# Peripherals.net
KiCad netlist of a schematic drawn in Altium Designer
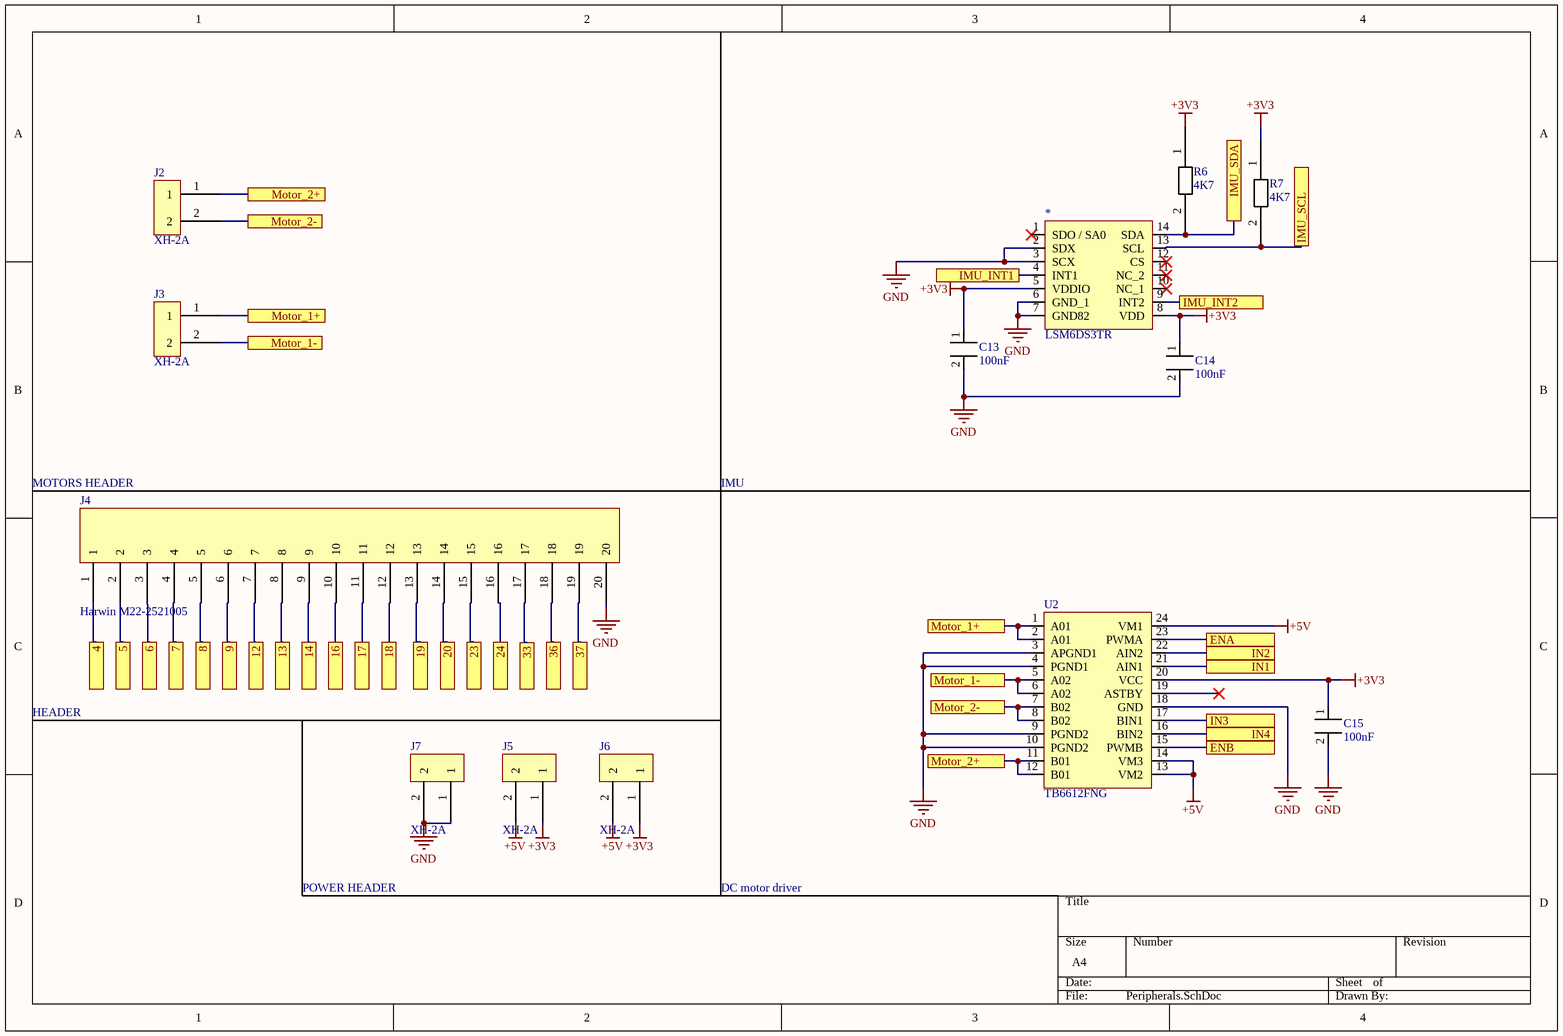
[diagram p0: Peripherals.SchDoc]

(export (version "E")
  (design (tool "Eeschema 10.0.6"))
  (components
    (comp (ref "*")
      (value "LSM6DS3TR")
      (footprint "LSM6DS3TR")
      (libsource (lib "Schlib1") (part "LSM6DS3TR"))
    )
    (comp (ref "C13") (value "100nF") (footprint "Condo") (libsource (lib "Schlib1") (part "CAPA")))
    (comp (ref "C14") (value "100nF") (footprint "Condo") (libsource (lib "Schlib1") (part "CAPA")))
    (comp (ref "C15") (value "100nF") (footprint "Condo") (libsource (lib "Schlib1") (part "CAPA")))
    (comp (ref "J2") (value "XH-2A") (footprint "XH-2A") (libsource (lib "") (part "XH-2A_1")))
    (comp (ref "J3") (value "XH-2A") (footprint "XH-2A") (libsource (lib "") (part "XH-2A_1")))
    (comp (ref "J4")
      (value "Harwin M22-2521005")
      (footprint "M22-2521005")
      (libsource (lib "Schlib1") (part "Harwin M22-2521005"))
    )
    (comp (ref "J5") (value "XH-2A") (footprint "XH-2A") (libsource (lib "Schlib1") (part "XH-2A")))
    (comp (ref "J6") (value "XH-2A") (footprint "XH-2A") (libsource (lib "Schlib1") (part "XH-2A")))
    (comp (ref "J7") (value "XH-2A") (footprint "XH-2A") (libsource (lib "Schlib1") (part "XH-2A")))
    (comp (ref "R6") (value "4K7") (footprint "Resistor") (libsource (lib "Schlib1") (part "Resistor")))
    (comp (ref "R7") (value "4K7") (footprint "Resistor") (libsource (lib "Schlib1") (part "Resistor")))
    (comp (ref "U2")
      (value "TB6612FNG")
      (footprint "TB6612FNG")
      (libsource (lib "Schlib1") (part "TB6612FNG"))
    )
  )
  (nets
    (net (code "1") (name "+3V3") (class "Default")
      (node (ref "*") (pin "5") (pinfunction "VDDIO_5") (pintype "passive"))
      (node (ref "*") (pin "8") (pinfunction "VDD_8") (pintype "passive"))
      (node (ref "C13") (pin "1") (pinfunction "IN_1") (pintype "passive"))
      (node (ref "C14") (pin "1") (pinfunction "IN_1") (pintype "passive"))
      (node (ref "C15") (pin "1") (pinfunction "IN_1") (pintype "passive"))
      (node (ref "J5") (pin "1") (pinfunction "1_1") (pintype "passive"))
      (node (ref "J6") (pin "1") (pinfunction "1_1") (pintype "passive"))
      (node (ref "R6") (pin "1") (pinfunction "1_1") (pintype "passive"))
      (node (ref "R7") (pin "1") (pinfunction "1_1") (pintype "passive"))
      (node (ref "U2") (pin "20") (pinfunction "VCC_20") (pintype "passive"))
    )
    (net (code "2") (name "+5V") (class "Default")
      (node (ref "J5") (pin "2") (pinfunction "2_2") (pintype "passive"))
      (node (ref "J6") (pin "2") (pinfunction "2_2") (pintype "passive"))
      (node (ref "U2") (pin "13") (pinfunction "VM2_13") (pintype "passive"))
      (node (ref "U2") (pin "14") (pinfunction "VM3_14") (pintype "passive"))
      (node (ref "U2") (pin "24") (pinfunction "VM1_24") (pintype "passive"))
    )
    (net (code "3") (name "/4") (class "Default")
      (node (ref "J4") (pin "1") (pinfunction "1_1") (pintype "passive"))
    )
    (net (code "4") (name "/5") (class "Default")
      (node (ref "J4") (pin "2") (pinfunction "2_2") (pintype "passive"))
    )
    (net (code "5") (name "/6") (class "Default")
      (node (ref "J4") (pin "3") (pinfunction "3_3") (pintype "passive"))
    )
    (net (code "6") (name "/7") (class "Default")
      (node (ref "J4") (pin "4") (pinfunction "4_4") (pintype "passive"))
    )
    (net (code "7") (name "/8") (class "Default")
      (node (ref "J4") (pin "5") (pinfunction "5_5") (pintype "passive"))
    )
    (net (code "8") (name "/9") (class "Default")
      (node (ref "J4") (pin "6") (pinfunction "6_6") (pintype "passive"))
    )
    (net (code "9") (name "/12") (class "Default")
      (node (ref "J4") (pin "7") (pinfunction "7_7") (pintype "passive"))
    )
    (net (code "10") (name "/13") (class "Default")
      (node (ref "J4") (pin "8") (pinfunction "8_8") (pintype "passive"))
    )
    (net (code "11") (name "/14") (class "Default")
      (node (ref "J4") (pin "9") (pinfunction "9_9") (pintype "passive"))
    )
    (net (code "12") (name "/16") (class "Default")
      (node (ref "J4") (pin "10") (pinfunction "10_10") (pintype "passive"))
    )
    (net (code "13") (name "/17") (class "Default")
      (node (ref "J4") (pin "11") (pinfunction "11_11") (pintype "passive"))
    )
    (net (code "14") (name "/18") (class "Default")
      (node (ref "J4") (pin "12") (pinfunction "12_12") (pintype "passive"))
    )
    (net (code "15") (name "/19") (class "Default")
      (node (ref "J4") (pin "13") (pinfunction "13_13") (pintype "passive"))
    )
    (net (code "16") (name "/20") (class "Default")
      (node (ref "J4") (pin "14") (pinfunction "14_14") (pintype "passive"))
    )
    (net (code "17") (name "/23") (class "Default")
      (node (ref "J4") (pin "15") (pinfunction "15_15") (pintype "passive"))
    )
    (net (code "18") (name "/24") (class "Default")
      (node (ref "J4") (pin "16") (pinfunction "16_16") (pintype "passive"))
    )
    (net (code "19") (name "/33") (class "Default")
      (node (ref "J4") (pin "17") (pinfunction "17_17") (pintype "passive"))
    )
    (net (code "20") (name "/36") (class "Default")
      (node (ref "J4") (pin "18") (pinfunction "18_18") (pintype "passive"))
    )
    (net (code "21") (name "/37") (class "Default")
      (node (ref "J4") (pin "19") (pinfunction "19_19") (pintype "passive"))
    )
    (net (code "22") (name "/ENA") (class "Default")
      (node (ref "U2") (pin "23") (pinfunction "PWMA_23") (pintype "passive"))
    )
    (net (code "23") (name "/ENB") (class "Default")
      (node (ref "U2") (pin "15") (pinfunction "PWMB_15") (pintype "passive"))
    )
    (net (code "24") (name "/IMU_INT1") (class "Default")
      (node (ref "*") (pin "4") (pinfunction "INT1_4") (pintype "passive"))
    )
    (net (code "25") (name "/IMU_INT2") (class "Default")
      (node (ref "*") (pin "9") (pinfunction "INT2_9") (pintype "passive"))
    )
    (net (code "26") (name "/IMU_SCL") (class "Default")
      (node (ref "*") (pin "13") (pinfunction "SCL_13") (pintype "passive"))
      (node (ref "R7") (pin "2") (pinfunction "2_2") (pintype "passive"))
    )
    (net (code "27") (name "/IMU_SDA") (class "Default")
      (node (ref "*") (pin "14") (pinfunction "SDA_14") (pintype "passive"))
      (node (ref "R6") (pin "2") (pinfunction "2_2") (pintype "passive"))
    )
    (net (code "28") (name "/IN1") (class "Default")
      (node (ref "U2") (pin "21") (pinfunction "AIN1_21") (pintype "passive"))
    )
    (net (code "29") (name "/IN2") (class "Default")
      (node (ref "U2") (pin "22") (pinfunction "AIN2_22") (pintype "passive"))
    )
    (net (code "30") (name "/IN3") (class "Default")
      (node (ref "U2") (pin "17") (pinfunction "BIN1_17") (pintype "passive"))
    )
    (net (code "31") (name "/IN4") (class "Default")
      (node (ref "U2") (pin "16") (pinfunction "BIN2_16") (pintype "passive"))
    )
    (net (code "32") (name "/Motor_1+") (class "Default")
      (node (ref "J3") (pin "1") (pinfunction "1_1") (pintype "passive"))
      (node (ref "U2") (pin "1") (pinfunction "A01_1") (pintype "passive"))
      (node (ref "U2") (pin "2") (pinfunction "A01_2") (pintype "passive"))
    )
    (net (code "33") (name "/Motor_1-") (class "Default")
      (node (ref "J3") (pin "2") (pinfunction "2_2") (pintype "passive"))
      (node (ref "U2") (pin "5") (pinfunction "A02_5") (pintype "passive"))
      (node (ref "U2") (pin "6") (pinfunction "A02_6") (pintype "passive"))
    )
    (net (code "34") (name "/Motor_2+") (class "Default")
      (node (ref "J2") (pin "1") (pinfunction "1_1") (pintype "passive"))
      (node (ref "U2") (pin "11") (pinfunction "B01_11") (pintype "passive"))
      (node (ref "U2") (pin "12") (pinfunction "B01_12") (pintype "passive"))
    )
    (net (code "35") (name "/Motor_2-") (class "Default")
      (node (ref "J2") (pin "2") (pinfunction "2_2") (pintype "passive"))
      (node (ref "U2") (pin "7") (pinfunction "B02_7") (pintype "passive"))
      (node (ref "U2") (pin "8") (pinfunction "B02_8") (pintype "passive"))
    )
    (net (code "36") (name "GND") (class "Default")
      (node (ref "*") (pin "2") (pinfunction "SDX_2") (pintype "passive"))
      (node (ref "*") (pin "3") (pinfunction "SCX_3") (pintype "passive"))
      (node (ref "*") (pin "6") (pinfunction "GND_1_6") (pintype "passive"))
      (node (ref "*") (pin "7") (pinfunction "GND82_7") (pintype "passive"))
      (node (ref "C13") (pin "2") (pinfunction "OUT_2") (pintype "passive"))
      (node (ref "C14") (pin "2") (pinfunction "OUT_2") (pintype "passive"))
      (node (ref "C15") (pin "2") (pinfunction "OUT_2") (pintype "passive"))
      (node (ref "J4") (pin "20") (pinfunction "20_20") (pintype "passive"))
      (node (ref "J7") (pin "1") (pinfunction "1_1") (pintype "passive"))
      (node (ref "J7") (pin "2") (pinfunction "2_2") (pintype "passive"))
      (node (ref "U2") (pin "10") (pinfunction "PGND2_10") (pintype "passive"))
      (node (ref "U2") (pin "18") (pinfunction "GND_18") (pintype "passive"))
      (node (ref "U2") (pin "3") (pinfunction "APGND1_3") (pintype "passive"))
      (node (ref "U2") (pin "4") (pinfunction "PGND1_4") (pintype "passive"))
      (node (ref "U2") (pin "9") (pinfunction "PGND2_9") (pintype "passive"))
    )
    (net (code "37") (name "unconnected-(*-CS-Pad12)") (class "Default")
      (node (ref "*") (pin "12") (pinfunction "CS_12") (pintype "passive+no_connect"))
    )
    (net (code "38") (name "unconnected-(*-NC_1-Pad10)") (class "Default")
      (node (ref "*") (pin "10") (pinfunction "NC_1_10") (pintype "passive+no_connect"))
    )
    (net (code "39") (name "unconnected-(*-NC_2-Pad11)") (class "Default")
      (node (ref "*") (pin "11") (pinfunction "NC_2_11") (pintype "passive+no_connect"))
    )
    (net (code "40") (name "unconnected-(*-SDO_{slash}_SA0-Pad1)") (class "Default")
      (node (ref "*") (pin "1") (pinfunction "SDO_/_SA0_1") (pintype "passive+no_connect"))
    )
    (net (code "41") (name "unconnected-(U2-ASTBY-Pad19)") (class "Default")
      (node (ref "U2") (pin "19") (pinfunction "ASTBY_19") (pintype "passive+no_connect"))
    )
  )
)
